# Motor_Driver.net
KiCad netlist of a schematic drawn in EAGLE
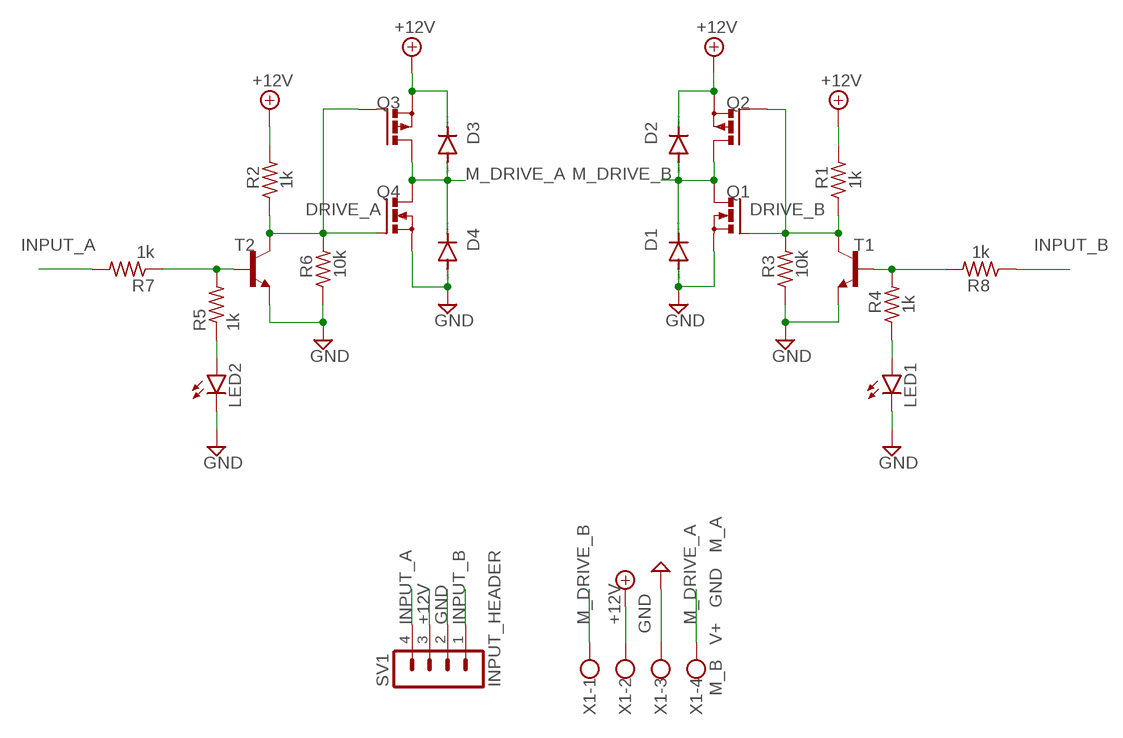
[diagram p0: schematic, sheet 1]

(export (version "E")
  (design (tool "Eeschema 10.0.6"))
  (components
    (comp (ref "D1")
      (value "1N4148DO35-10")
      (footprint "eagle-import:DO35-10")
      (libsource (lib "eagle-import") (part "1N4148DO35-10"))
    )
    (comp (ref "D2")
      (value "1N4148DO35-10")
      (footprint "eagle-import:DO35-10")
      (libsource (lib "eagle-import") (part "1N4148DO35-10"))
    )
    (comp (ref "D3")
      (value "1N4148DO35-10")
      (footprint "eagle-import:DO35-10")
      (libsource (lib "eagle-import") (part "1N4148DO35-10"))
    )
    (comp (ref "D4")
      (value "1N4148DO35-10")
      (footprint "eagle-import:DO35-10")
      (libsource (lib "eagle-import") (part "1N4148DO35-10"))
    )
    (comp (ref "LED1")
      (value "LED_B")
      (footprint "eagle-import:LED5MM")
      (libsource (lib "eagle-import") (part "LED5MM"))
    )
    (comp (ref "LED2")
      (value "LED_A")
      (footprint "eagle-import:LED5MM")
      (libsource (lib "eagle-import") (part "LED5MM"))
    )
    (comp (ref "Q1")
      (value "N_B")
      (footprint "eagle-import:TO220BV")
      (libsource (lib "eagle-import") (part "PMOSFET_NTO220BV"))
    )
    (comp (ref "Q2")
      (value "P_B")
      (footprint "eagle-import:TO220BV")
      (libsource (lib "eagle-import") (part "PMOSFET_PTO220BV"))
    )
    (comp (ref "Q3")
      (value "P_A")
      (footprint "eagle-import:TO220BV")
      (libsource (lib "eagle-import") (part "PMOSFET_PTO220BV"))
    )
    (comp (ref "Q4")
      (value "N_A")
      (footprint "eagle-import:TO220BV")
      (libsource (lib "eagle-import") (part "PMOSFET_NTO220BV"))
    )
    (comp (ref "R1")
      (value "1k")
      (footprint "eagle-import:0207_10")
      (libsource (lib "eagle-import") (part "R-US_0207/10"))
    )
    (comp (ref "R2")
      (value "1k")
      (footprint "eagle-import:0207_10")
      (libsource (lib "eagle-import") (part "R-US_0207/10"))
    )
    (comp (ref "R3")
      (value "10k")
      (footprint "eagle-import:0207_10")
      (libsource (lib "eagle-import") (part "R-US_0207/10"))
    )
    (comp (ref "R4")
      (value "1k")
      (footprint "eagle-import:0207_10")
      (libsource (lib "eagle-import") (part "R-US_0207/10"))
    )
    (comp (ref "R5")
      (value "1k")
      (footprint "eagle-import:0207_10")
      (libsource (lib "eagle-import") (part "R-US_0207/10"))
    )
    (comp (ref "R6")
      (value "10k")
      (footprint "eagle-import:0207_10")
      (libsource (lib "eagle-import") (part "R-US_0207/10"))
    )
    (comp (ref "R7")
      (value "1k")
      (footprint "eagle-import:0207_10")
      (libsource (lib "eagle-import") (part "R-US_0207/10"))
    )
    (comp (ref "R8")
      (value "1k")
      (footprint "eagle-import:0207_10")
      (libsource (lib "eagle-import") (part "R-US_0207/10"))
    )
    (comp (ref "SV1")
      (value "INPUT_HEADER")
      (footprint "eagle-import:MA04-1")
      (libsource (lib "eagle-import") (part "MA04-1"))
    )
    (comp (ref "T1")
      (value "2N3904")
      (footprint "eagle-import:TO92")
      (libsource (lib "eagle-import") (part "2N3904"))
    )
    (comp (ref "T2")
      (value "2N3904")
      (footprint "eagle-import:TO92")
      (libsource (lib "eagle-import") (part "2N3904"))
    )
    (comp (ref "X1")
      (value "M_B V+ GND M_A")
      (footprint "eagle-import:W237-4")
      (libsource (lib "eagle-import") (part "W237-4"))
    )
  )
  (nets
    (net (code "1") (name "+12V") (class "Default")
      (node (ref "D2") (pin "C") (pinfunction "C_C") (pintype "passive"))
      (node (ref "D3") (pin "C") (pinfunction "C_C") (pintype "passive"))
      (node (ref "Q2") (pin "S") (pinfunction "S_S") (pintype "passive"))
      (node (ref "Q3") (pin "S") (pinfunction "S_S") (pintype "passive"))
      (node (ref "R1") (pin "2") (pinfunction "2_2") (pintype "passive"))
      (node (ref "R2") (pin "2") (pinfunction "2_2") (pintype "passive"))
      (node (ref "SV1") (pin "3") (pinfunction "3_3") (pintype "passive"))
      (node (ref "X1") (pin "2") (pinfunction "KL_2") (pintype "passive"))
    )
    (net (code "2") (name "/DRIVE_A") (class "Default")
      (node (ref "Q3") (pin "G") (pinfunction "G_G") (pintype "passive"))
      (node (ref "Q4") (pin "G") (pinfunction "G_G") (pintype "passive"))
      (node (ref "R2") (pin "1") (pinfunction "1_1") (pintype "passive"))
      (node (ref "R6") (pin "2") (pinfunction "2_2") (pintype "passive"))
      (node (ref "T2") (pin "1") (pinfunction "C_1") (pintype "passive"))
    )
    (net (code "3") (name "/DRIVE_B") (class "Default")
      (node (ref "Q1") (pin "G") (pinfunction "G_G") (pintype "passive"))
      (node (ref "Q2") (pin "G") (pinfunction "G_G") (pintype "passive"))
      (node (ref "R1") (pin "1") (pinfunction "1_1") (pintype "passive"))
      (node (ref "R3") (pin "2") (pinfunction "2_2") (pintype "passive"))
      (node (ref "T1") (pin "1") (pinfunction "C_1") (pintype "passive"))
    )
    (net (code "4") (name "/INPUT_A") (class "Default")
      (node (ref "R7") (pin "2") (pinfunction "2_2") (pintype "passive"))
      (node (ref "SV1") (pin "4") (pinfunction "4_4") (pintype "passive"))
    )
    (net (code "5") (name "/INPUT_B") (class "Default")
      (node (ref "R8") (pin "1") (pinfunction "1_1") (pintype "passive"))
      (node (ref "SV1") (pin "1") (pinfunction "1_1") (pintype "passive"))
    )
    (net (code "6") (name "/M_DRIVE_A") (class "Default")
      (node (ref "D3") (pin "A") (pinfunction "A_A") (pintype "passive"))
      (node (ref "D4") (pin "C") (pinfunction "C_C") (pintype "passive"))
      (node (ref "Q3") (pin "D") (pinfunction "D_D") (pintype "passive"))
      (node (ref "Q4") (pin "D") (pinfunction "D_D") (pintype "passive"))
      (node (ref "X1") (pin "4") (pinfunction "KL_4") (pintype "passive"))
    )
    (net (code "7") (name "/M_DRIVE_B") (class "Default")
      (node (ref "D1") (pin "C") (pinfunction "C_C") (pintype "passive"))
      (node (ref "D2") (pin "A") (pinfunction "A_A") (pintype "passive"))
      (node (ref "Q1") (pin "D") (pinfunction "D_D") (pintype "passive"))
      (node (ref "Q2") (pin "D") (pinfunction "D_D") (pintype "passive"))
      (node (ref "X1") (pin "1") (pinfunction "KL_1") (pintype "passive"))
    )
    (net (code "8") (name "GND") (class "Default")
      (node (ref "D1") (pin "A") (pinfunction "A_A") (pintype "passive"))
      (node (ref "D4") (pin "A") (pinfunction "A_A") (pintype "passive"))
      (node (ref "LED1") (pin "K") (pinfunction "C_K") (pintype "passive"))
      (node (ref "LED2") (pin "K") (pinfunction "C_K") (pintype "passive"))
      (node (ref "Q1") (pin "S") (pinfunction "S_S") (pintype "passive"))
      (node (ref "Q4") (pin "S") (pinfunction "S_S") (pintype "passive"))
      (node (ref "R3") (pin "1") (pinfunction "1_1") (pintype "passive"))
      (node (ref "R6") (pin "1") (pinfunction "1_1") (pintype "passive"))
      (node (ref "SV1") (pin "2") (pinfunction "2_2") (pintype "passive"))
      (node (ref "T1") (pin "3") (pinfunction "E_3") (pintype "passive"))
      (node (ref "T2") (pin "3") (pinfunction "E_3") (pintype "passive"))
      (node (ref "X1") (pin "3") (pinfunction "KL_3") (pintype "passive"))
    )
    (net (code "9") (name "Net-(LED1-PadA)") (class "Default")
      (node (ref "LED1") (pin "A") (pinfunction "A_A") (pintype "passive"))
      (node (ref "R4") (pin "1") (pinfunction "1_1") (pintype "passive"))
    )
    (net (code "10") (name "Net-(LED2-PadA)") (class "Default")
      (node (ref "LED2") (pin "A") (pinfunction "A_A") (pintype "passive"))
      (node (ref "R5") (pin "1") (pinfunction "1_1") (pintype "passive"))
    )
    (net (code "11") (name "Net-(T1-B)") (class "Default")
      (node (ref "R4") (pin "2") (pinfunction "2_2") (pintype "passive"))
      (node (ref "R8") (pin "2") (pinfunction "2_2") (pintype "passive"))
      (node (ref "T1") (pin "2") (pinfunction "B_2") (pintype "passive"))
    )
    (net (code "12") (name "Net-(T2-B)") (class "Default")
      (node (ref "R5") (pin "2") (pinfunction "2_2") (pintype "passive"))
      (node (ref "R7") (pin "1") (pinfunction "1_1") (pintype "passive"))
      (node (ref "T2") (pin "2") (pinfunction "B_2") (pintype "passive"))
    )
  )
)
